# USBSerial.net
KiCad netlist of a schematic drawn in Altium Designer
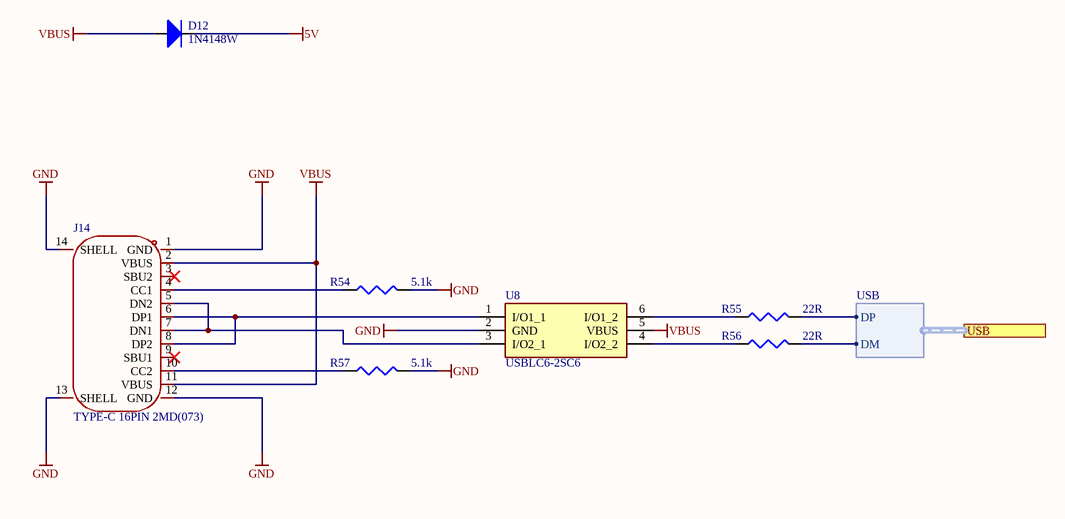
[diagram p0: USBSerial.SchDoc]

(export (version "E")
  (design (tool "Eeschema 10.0.6"))
  (components
    (comp (ref "D12")
      (value "1N4148W")
      (footprint "VESC_BMS:SOD123")
      (description "Diode, Vrrm: 100V, If: 0.15A, Vf: 1V")
      (libsource (lib "AR_Diodes") (part "MMSD4148T1G"))
    )
    (comp (ref "J14")
      (value "TYPE-C 16PIN 2MD(073)")
      (footprint "VESC_BMS:USB-C-SMD_TYPE-C-6PIN-2MD-073")
      (fields (field (name "MANUFACTURER") "SHOU HAN(首韩)"))
      (libsource (lib "VESC_BMS") (part "TYPE-C 16PIN 2MD(073)"))
    )
    (comp (ref "R54")
      (value "5.1k")
      (footprint "VESC_BMS:0402")
      (description "Resistor, 240, 0.1%, 0.0625W, 50V, 100PPM, 0402")
      (libsource (lib "AR_Resistors_SMD") (part "240/0402/0063W/50V"))
    )
    (comp (ref "R55")
      (value "22R")
      (footprint "VESC_BMS:0402")
      (description "Resistor, 240, 0.1%, 0.0625W, 50V, 100PPM, 0402")
      (libsource (lib "AR_Resistors_SMD") (part "240/0402/0063W/50V"))
    )
    (comp (ref "R56")
      (value "22R")
      (footprint "VESC_BMS:0402")
      (description "Resistor, 240, 0.1%, 0.0625W, 50V, 100PPM, 0402")
      (libsource (lib "AR_Resistors_SMD") (part "240/0402/0063W/50V"))
    )
    (comp (ref "R57")
      (value "5.1k")
      (footprint "VESC_BMS:0402")
      (description "Resistor, 240, 0.1%, 0.0625W, 50V, 100PPM, 0402")
      (libsource (lib "AR_Resistors_SMD") (part "240/0402/0063W/50V"))
    )
    (comp (ref "U8")
      (value "USBLC6-2SC6")
      (footprint "VESC_BMS:SOT95P280X145-6N")
      (description "Integrated Circuit")
      (fields (field (name "MOUSER PART NUMBER") "511-USBLC6-2SC6"))
      (libsource (lib "DB10005_DieBieMS") (part "USBLC6-2SC6"))
    )
  )
  (nets
    (net (code "2") (name "/DM") (class "Default")
      (node (ref "R56") (pin "2") (pinfunction "2_2") (pintype "passive"))
    )
    (net (code "3") (name "/DP") (class "Default")
      (node (ref "R55") (pin "2") (pinfunction "2_2") (pintype "passive"))
    )
    (net (code "5") (name "5V") (class "Default")
      (node (ref "D12") (pin "2") (pinfunction "K_2") (pintype "passive"))
    )
    (net (code "6") (name "GND") (class "Default")
      (node (ref "J14") (pin "1") (pinfunction "GND_1") (pintype "passive"))
      (node (ref "J14") (pin "12") (pinfunction "GND_12") (pintype "passive"))
      (node (ref "J14") (pin "13") (pinfunction "SHELL_13") (pintype "passive"))
      (node (ref "J14") (pin "14") (pinfunction "SHELL_14") (pintype "passive"))
      (node (ref "R54") (pin "2") (pinfunction "2_2") (pintype "passive"))
      (node (ref "R57") (pin "2") (pinfunction "2_2") (pintype "passive"))
      (node (ref "U8") (pin "2") (pinfunction "GND_2") (pintype "passive"))
    )
    (net (code "7") (name "Net-(J14-CC1)") (class "Default")
      (node (ref "J14") (pin "4") (pinfunction "CC1_4") (pintype "passive"))
      (node (ref "R54") (pin "1") (pinfunction "1_1") (pintype "passive"))
    )
    (net (code "8") (name "Net-(J14-CC2)") (class "Default")
      (node (ref "J14") (pin "10") (pinfunction "CC2_10") (pintype "passive"))
      (node (ref "R57") (pin "1") (pinfunction "1_1") (pintype "passive"))
    )
    (net (code "9") (name "Net-(J14-DN1)") (class "Default")
      (node (ref "J14") (pin "5") (pinfunction "DN2_5") (pintype "passive"))
      (node (ref "J14") (pin "7") (pinfunction "DN1_7") (pintype "passive"))
      (node (ref "U8") (pin "3") (pinfunction "I/O2_1_3") (pintype "passive"))
    )
    (net (code "10") (name "Net-(J14-DP1)") (class "Default")
      (node (ref "J14") (pin "6") (pinfunction "DP1_6") (pintype "passive"))
      (node (ref "J14") (pin "8") (pinfunction "DP2_8") (pintype "passive"))
      (node (ref "U8") (pin "1") (pinfunction "I/O1_1_1") (pintype "passive"))
    )
    (net (code "11") (name "Net-(U8-I{slash}O1_2)") (class "Default")
      (node (ref "R55") (pin "1") (pinfunction "1_1") (pintype "passive"))
      (node (ref "U8") (pin "6") (pinfunction "I/O1_2_6") (pintype "passive"))
    )
    (net (code "12") (name "Net-(U8-I{slash}O2_2)") (class "Default")
      (node (ref "R56") (pin "1") (pinfunction "1_1") (pintype "passive"))
      (node (ref "U8") (pin "4") (pinfunction "I/O2_2_4") (pintype "passive"))
    )
    (net (code "13") (name "VBUS") (class "Default")
      (node (ref "D12") (pin "1") (pinfunction "A_1") (pintype "passive"))
      (node (ref "J14") (pin "11") (pinfunction "VBUS_11") (pintype "passive"))
      (node (ref "J14") (pin "2") (pinfunction "VBUS_2") (pintype "passive"))
      (node (ref "U8") (pin "5") (pinfunction "VBUS_5") (pintype "passive"))
    )
    (net (code "14") (name "unconnected-(J14-SBU1-Pad9)") (class "Default")
      (node (ref "J14") (pin "9") (pinfunction "SBU1_9") (pintype "passive+no_connect"))
    )
    (net (code "15") (name "unconnected-(J14-SBU2-Pad3)") (class "Default")
      (node (ref "J14") (pin "3") (pinfunction "SBU2_3") (pintype "passive+no_connect"))
    )
  )
)
